# eMMC.net
KiCad netlist of a schematic drawn in Altium Designer
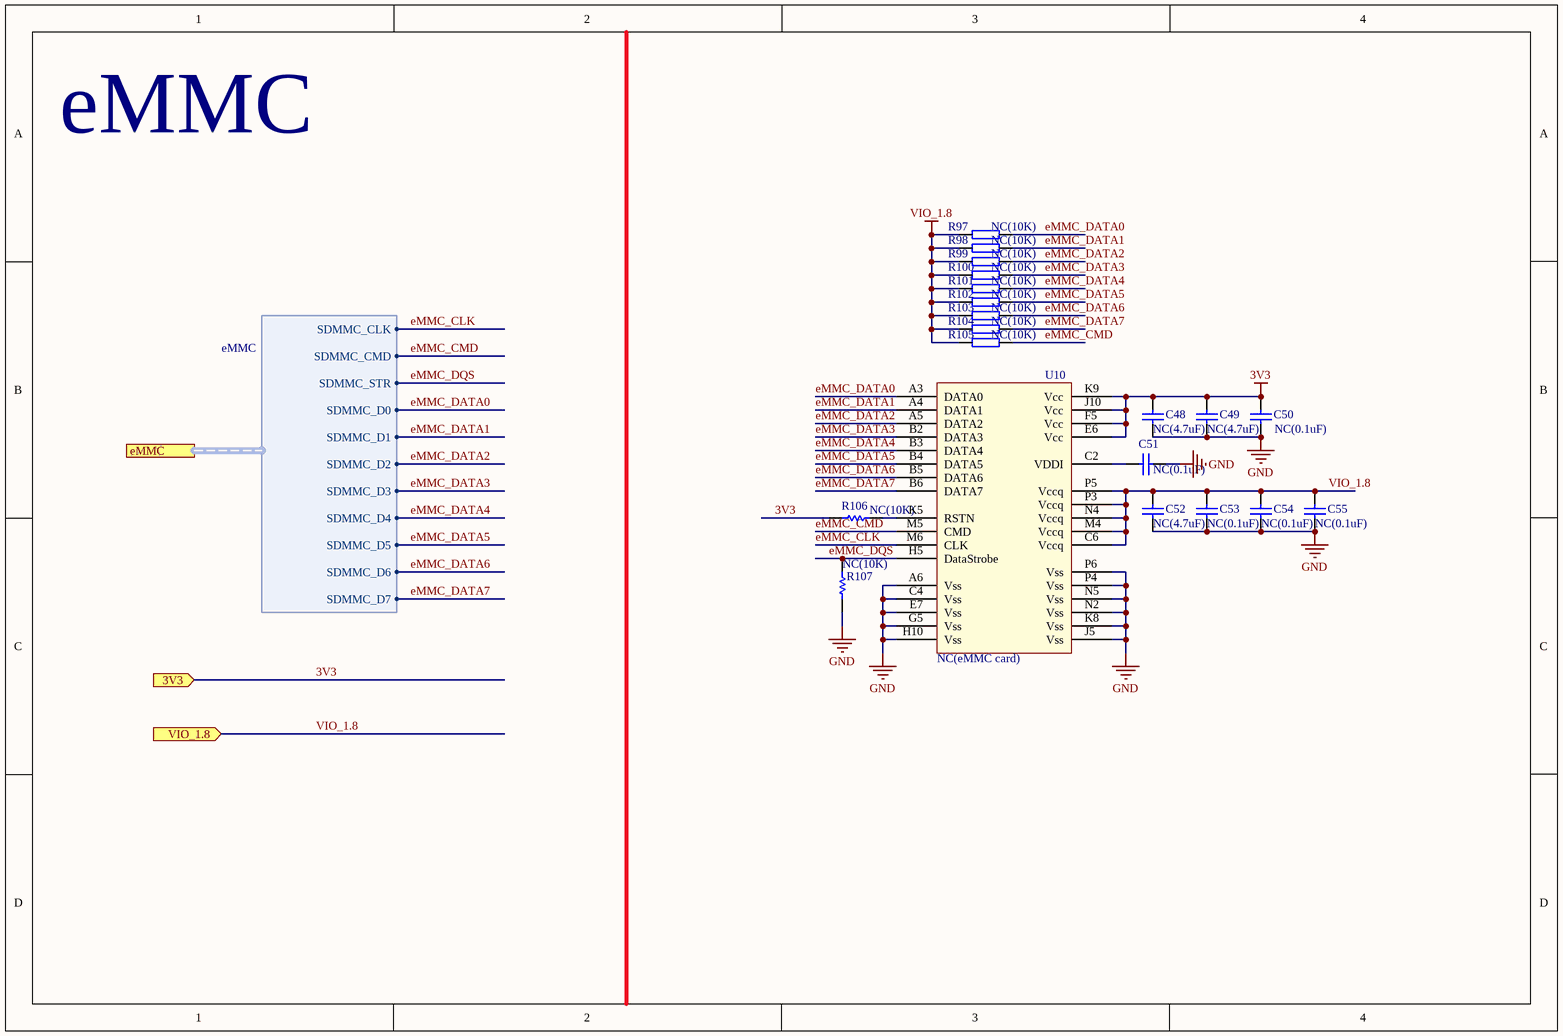
[diagram p0: eMMC.SchDoc]

(export (version "E")
  (design (tool "Eeschema 10.0.6"))
  (components
    (comp (ref "C48")
      (value "NC(4.7uF)")
      (footprint "0402_C")
      (description "Capacitor")
      (fields (field (name "PUBLISHER") "Altium Limited"))
      (libsource (lib "Miscellaneous Devices") (part "Cap"))
    )
    (comp (ref "C49")
      (value "NC(4.7uF)")
      (footprint "0402_C")
      (description "Capacitor")
      (fields (field (name "PUBLISHER") "Altium Limited"))
      (libsource (lib "Miscellaneous Devices") (part "Cap"))
    )
    (comp (ref "C50")
      (value "NC(0.1uF)")
      (footprint "0402_C")
      (description "Capacitor")
      (fields (field (name "PUBLISHER") "Altium Limited"))
      (libsource (lib "Miscellaneous Devices") (part "Cap"))
    )
    (comp (ref "C51")
      (value "NC(0.1uF)")
      (footprint "0402_C")
      (description "Capacitor")
      (fields (field (name "PUBLISHER") "Altium Limited"))
      (libsource (lib "Miscellaneous Devices") (part "Cap"))
    )
    (comp (ref "C52")
      (value "NC(4.7uF)")
      (footprint "0402_C")
      (description "Capacitor")
      (fields (field (name "PUBLISHER") "Altium Limited"))
      (libsource (lib "Miscellaneous Devices") (part "Cap"))
    )
    (comp (ref "C53")
      (value "NC(0.1uF)")
      (footprint "0402_C")
      (description "Capacitor")
      (fields (field (name "PUBLISHER") "Altium Limited"))
      (libsource (lib "Miscellaneous Devices") (part "Cap"))
    )
    (comp (ref "C54")
      (value "NC(0.1uF)")
      (footprint "0402_C")
      (description "Capacitor")
      (fields (field (name "PUBLISHER") "Altium Limited"))
      (libsource (lib "Miscellaneous Devices") (part "Cap"))
    )
    (comp (ref "C55")
      (value "NC(0.1uF)")
      (footprint "0402_C")
      (description "Capacitor")
      (fields (field (name "PUBLISHER") "Altium Limited"))
      (libsource (lib "Miscellaneous Devices") (part "Cap"))
    )
    (comp (ref "R97") (value "NC(10K)") (footprint "0402") (libsource (lib "*") (part "RES")))
    (comp (ref "R98") (value "NC(10K)") (footprint "0402") (libsource (lib "*") (part "RES")))
    (comp (ref "R99") (value "NC(10K)") (footprint "0402") (libsource (lib "*") (part "RES")))
    (comp (ref "R100") (value "NC(10K)") (footprint "0402") (libsource (lib "*") (part "RES")))
    (comp (ref "R101") (value "NC(10K)") (footprint "0402") (libsource (lib "*") (part "RES")))
    (comp (ref "R102") (value "NC(10K)") (footprint "0402") (libsource (lib "*") (part "RES")))
    (comp (ref "R103") (value "NC(10K)") (footprint "0402") (libsource (lib "*") (part "RES")))
    (comp (ref "R104") (value "NC(10K)") (footprint "0402") (libsource (lib "*") (part "RES")))
    (comp (ref "R105") (value "NC(10K)") (footprint "0402") (libsource (lib "*") (part "RES")))
    (comp (ref "R106")
      (value "NC(10K)")
      (footprint "0402")
      (description "Resistor")
      (fields (field (name "PUBLISHER") "Altium Limited"))
      (libsource (lib "Miscellaneous Devices") (part "Res1"))
    )
    (comp (ref "R107")
      (value "NC(10K)")
      (footprint "0402")
      (description "Resistor")
      (fields (field (name "PUBLISHER") "Altium Limited"))
      (libsource (lib "Miscellaneous Devices") (part "Res1"))
    )
    (comp (ref "U10")
      (value "NC(eMMC card)")
      (footprint "WFBGA-153-11.5x13x0.8mm")
      (libsource (lib "MySchlib") (part "KLM8G1GETF-B041"))
    )
  )
  (nets
    (net (code "2") (name "/eMMC_CLK") (class "Default")
      (node (ref "U10") (pin "M6") (pinfunction "CLK_M6") (pintype "passive"))
    )
    (net (code "3") (name "/eMMC_CMD") (class "Default")
      (node (ref "R105") (pin "1") (pintype "passive"))
      (node (ref "U10") (pin "M5") (pinfunction "CMD_M5") (pintype "passive"))
    )
    (net (code "4") (name "/eMMC_DATA0") (class "Default")
      (node (ref "R97") (pin "1") (pintype "passive"))
      (node (ref "U10") (pin "A3") (pinfunction "DATA0_A3") (pintype "passive"))
    )
    (net (code "5") (name "/eMMC_DATA1") (class "Default")
      (node (ref "R98") (pin "1") (pintype "passive"))
      (node (ref "U10") (pin "A4") (pinfunction "DATA1_A4") (pintype "passive"))
    )
    (net (code "6") (name "/eMMC_DATA2") (class "Default")
      (node (ref "R99") (pin "1") (pintype "passive"))
      (node (ref "U10") (pin "A5") (pinfunction "DATA2_A5") (pintype "passive"))
    )
    (net (code "7") (name "/eMMC_DATA3") (class "Default")
      (node (ref "R100") (pin "1") (pintype "passive"))
      (node (ref "U10") (pin "B2") (pinfunction "DATA3_B2") (pintype "passive"))
    )
    (net (code "8") (name "/eMMC_DATA4") (class "Default")
      (node (ref "R101") (pin "1") (pintype "passive"))
      (node (ref "U10") (pin "B3") (pinfunction "DATA4_B3") (pintype "passive"))
    )
    (net (code "9") (name "/eMMC_DATA5") (class "Default")
      (node (ref "R102") (pin "1") (pintype "passive"))
      (node (ref "U10") (pin "B4") (pinfunction "DATA5_B4") (pintype "passive"))
    )
    (net (code "10") (name "/eMMC_DATA6") (class "Default")
      (node (ref "R103") (pin "1") (pintype "passive"))
      (node (ref "U10") (pin "B5") (pinfunction "DATA6_B5") (pintype "passive"))
    )
    (net (code "11") (name "/eMMC_DATA7") (class "Default")
      (node (ref "R104") (pin "1") (pintype "passive"))
      (node (ref "U10") (pin "B6") (pinfunction "DATA7_B6") (pintype "passive"))
    )
    (net (code "12") (name "/eMMC_DQS") (class "Default")
      (node (ref "R107") (pin "1") (pinfunction "1_1") (pintype "passive"))
      (node (ref "U10") (pin "H5") (pinfunction "DataStrobe_H5") (pintype "passive"))
    )
    (net (code "14") (name "3V3") (class "Default")
      (node (ref "C48") (pin "2") (pinfunction "2_2") (pintype "passive"))
      (node (ref "C49") (pin "1") (pinfunction "1_1") (pintype "passive"))
      (node (ref "C50") (pin "1") (pinfunction "1_1") (pintype "passive"))
      (node (ref "R106") (pin "2") (pinfunction "2_2") (pintype "passive"))
      (node (ref "U10") (pin "E6") (pinfunction "Vcc_E6") (pintype "passive"))
      (node (ref "U10") (pin "F5") (pinfunction "Vcc_F5") (pintype "passive"))
      (node (ref "U10") (pin "J10") (pinfunction "Vcc_J10") (pintype "passive"))
      (node (ref "U10") (pin "K9") (pinfunction "Vcc_K9") (pintype "passive"))
    )
    (net (code "15") (name "GND") (class "Default")
      (node (ref "C48") (pin "1") (pinfunction "1_1") (pintype "passive"))
      (node (ref "C49") (pin "2") (pinfunction "2_2") (pintype "passive"))
      (node (ref "C50") (pin "2") (pinfunction "2_2") (pintype "passive"))
      (node (ref "C51") (pin "1") (pinfunction "1_1") (pintype "passive"))
      (node (ref "C52") (pin "1") (pinfunction "1_1") (pintype "passive"))
      (node (ref "C53") (pin "2") (pinfunction "2_2") (pintype "passive"))
      (node (ref "C54") (pin "2") (pinfunction "2_2") (pintype "passive"))
      (node (ref "C55") (pin "2") (pinfunction "2_2") (pintype "passive"))
      (node (ref "R107") (pin "2") (pinfunction "2_2") (pintype "passive"))
      (node (ref "U10") (pin "A6") (pinfunction "Vss_A6") (pintype "passive"))
      (node (ref "U10") (pin "C4") (pinfunction "Vss_C4") (pintype "passive"))
      (node (ref "U10") (pin "E7") (pinfunction "Vss_E7") (pintype "passive"))
      (node (ref "U10") (pin "G5") (pinfunction "Vss_G5") (pintype "passive"))
      (node (ref "U10") (pin "H10") (pinfunction "Vss_H10") (pintype "passive"))
      (node (ref "U10") (pin "J5") (pinfunction "Vss_J5") (pintype "passive"))
      (node (ref "U10") (pin "K8") (pinfunction "Vss_K8") (pintype "passive"))
      (node (ref "U10") (pin "N2") (pinfunction "Vss_N2") (pintype "passive"))
      (node (ref "U10") (pin "N5") (pinfunction "Vss_N5") (pintype "passive"))
      (node (ref "U10") (pin "P4") (pinfunction "Vss_P4") (pintype "passive"))
      (node (ref "U10") (pin "P6") (pinfunction "Vss_P6") (pintype "passive"))
    )
    (net (code "16") (name "Net-(U10-RSTN)") (class "Default")
      (node (ref "R106") (pin "1") (pinfunction "1_1") (pintype "passive"))
      (node (ref "U10") (pin "K5") (pinfunction "RSTN_K5") (pintype "passive"))
    )
    (net (code "17") (name "Net-(U10-VDDI)") (class "Default")
      (node (ref "C51") (pin "2") (pinfunction "2_2") (pintype "passive"))
      (node (ref "U10") (pin "C2") (pinfunction "VDDI_C2") (pintype "passive"))
    )
    (net (code "18") (name "VIO_1.8") (class "Default")
      (node (ref "C52") (pin "2") (pinfunction "2_2") (pintype "passive"))
      (node (ref "C53") (pin "1") (pinfunction "1_1") (pintype "passive"))
      (node (ref "C54") (pin "1") (pinfunction "1_1") (pintype "passive"))
      (node (ref "C55") (pin "1") (pinfunction "1_1") (pintype "passive"))
      (node (ref "R100") (pin "2") (pintype "passive"))
      (node (ref "R101") (pin "2") (pintype "passive"))
      (node (ref "R102") (pin "2") (pintype "passive"))
      (node (ref "R103") (pin "2") (pintype "passive"))
      (node (ref "R104") (pin "2") (pintype "passive"))
      (node (ref "R105") (pin "2") (pintype "passive"))
      (node (ref "R97") (pin "2") (pintype "passive"))
      (node (ref "R98") (pin "2") (pintype "passive"))
      (node (ref "R99") (pin "2") (pintype "passive"))
      (node (ref "U10") (pin "C6") (pinfunction "Vccq_C6") (pintype "passive"))
      (node (ref "U10") (pin "M4") (pinfunction "Vccq_M4") (pintype "passive"))
      (node (ref "U10") (pin "N4") (pinfunction "Vccq_N4") (pintype "passive"))
      (node (ref "U10") (pin "P3") (pinfunction "Vccq_P3") (pintype "passive"))
      (node (ref "U10") (pin "P5") (pinfunction "Vccq_P5") (pintype "passive"))
    )
  )
)
